# wiring.net
KiCad netlist of a schematic drawn in EAGLE
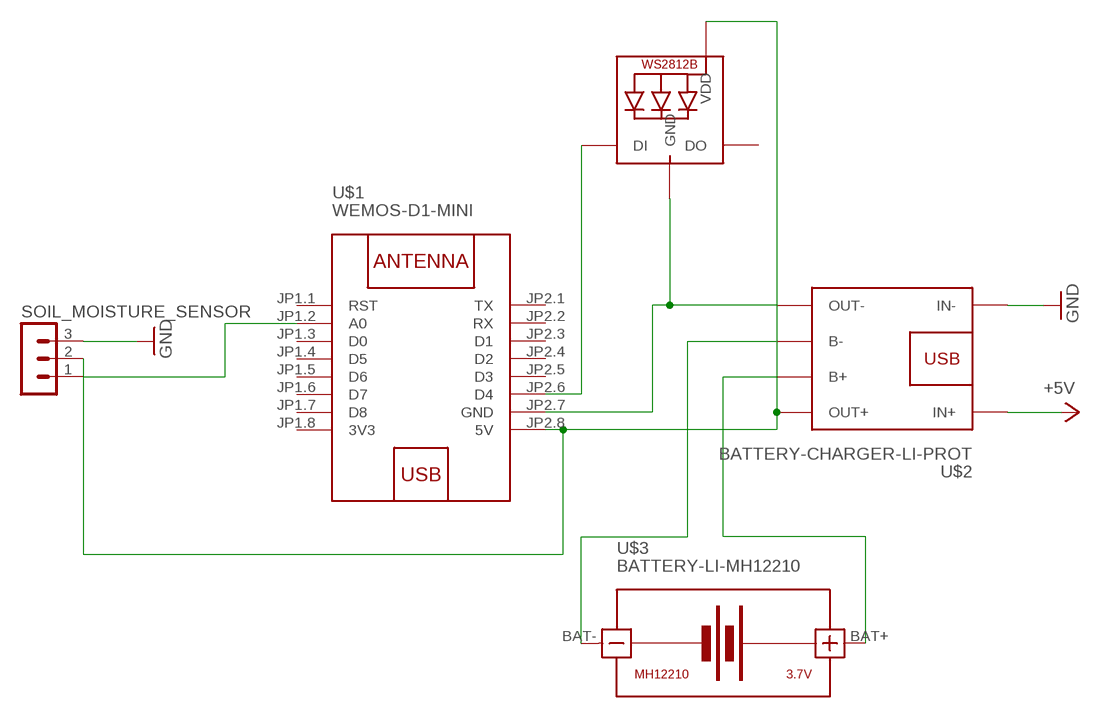
[diagram p0: schematic, sheet 1]

(export (version "E")
  (design (tool "Eeschema 10.0.6"))
  (components
    (comp (ref "LED1")
      (value "WS2812B3535")
      (footprint "eagle-import:LED3535")
      (libsource (lib "eagle-import") (part "WS2812B3535"))
    )
    (comp (ref "SOIL_MOISTURE_SENSOR")
      (value "MA03-1")
      (footprint "eagle-import:MA03-1")
      (libsource (lib "eagle-import") (part "MA03-1"))
    )
    (comp (ref "U$1")
      (value "WEMOS-D1-MINI")
      (footprint "eagle-import:WEMOS-D1-MINI")
      (libsource (lib "eagle-import") (part "WEMOS-D1-MINI"))
    )
    (comp (ref "U$2")
      (value "BATTERY-CHARGER-LI-PROT")
      (footprint "eagle-import:BATTERY-CHARGER-LI-PROT")
      (libsource (lib "eagle-import") (part "BATTERY-CHARGER-LI-PROT"))
    )
    (comp (ref "U$3")
      (value "BATTERY-LI-MH12210")
      (footprint "eagle-import:BATTERY-LI-MH12210")
      (libsource (lib "eagle-import") (part "BATTERY-LI-MH12210"))
    )
  )
  (nets
    (net (code "1") (name "+5V") (class "Default")
      (node (ref "U$2") (pin "IN+") (pinfunction "IN+_IN+") (pintype "bidirectional"))
    )
    (net (code "2") (name "/3V3") (class "Default")
      (node (ref "U$1") (pin "JP1.8") (pinfunction "3V3_JP1.8") (pintype "power_in"))
    )
    (net (code "3") (name "GND") (class "Default")
      (node (ref "SOIL_MOISTURE_SENSOR") (pin "3") (pinfunction "3_3") (pintype "passive"))
      (node (ref "U$2") (pin "IN-") (pinfunction "IN-_IN-") (pintype "bidirectional"))
    )
    (net (code "4") (name "Net-(LED1-DI)") (class "Default")
      (node (ref "LED1") (pin "1") (pinfunction "DI_1") (pintype "input"))
      (node (ref "U$1") (pin "JP2.6") (pinfunction "D4_JP2.6") (pintype "bidirectional"))
    )
    (net (code "5") (name "Net-(LED1-GND)") (class "Default")
      (node (ref "LED1") (pin "4") (pinfunction "GND_4") (pintype "power_in"))
      (node (ref "U$1") (pin "JP2.7") (pinfunction "GND_JP2.7") (pintype "power_in"))
      (node (ref "U$2") (pin "OUT-") (pinfunction "OUT-_OUT-") (pintype "bidirectional"))
    )
    (net (code "6") (name "Net-(LED1-VDD)") (class "Default")
      (node (ref "LED1") (pin "2") (pinfunction "VDD_2") (pintype "power_in"))
      (node (ref "SOIL_MOISTURE_SENSOR") (pin "2") (pinfunction "2_2") (pintype "passive"))
      (node (ref "U$1") (pin "JP2.8") (pinfunction "5V_JP2.8") (pintype "power_in"))
      (node (ref "U$2") (pin "OUT+") (pinfunction "OUT+_OUT+") (pintype "bidirectional"))
    )
    (net (code "7") (name "Net-(U$1-A0)") (class "Default")
      (node (ref "SOIL_MOISTURE_SENSOR") (pin "1") (pinfunction "1_1") (pintype "passive"))
      (node (ref "U$1") (pin "JP1.2") (pinfunction "A0_JP1.2") (pintype "bidirectional"))
    )
    (net (code "8") (name "Net-(U$2-PadB+)") (class "Default")
      (node (ref "U$2") (pin "B+") (pinfunction "B+_B+") (pintype "bidirectional"))
      (node (ref "U$3") (pin "BAT+") (pinfunction "BAT+_BAT+") (pintype "power_in"))
    )
    (net (code "9") (name "Net-(U$2-PadB-)") (class "Default")
      (node (ref "U$2") (pin "B-") (pinfunction "B-_B-") (pintype "bidirectional"))
      (node (ref "U$3") (pin "BAT-") (pinfunction "BAT-_BAT-") (pintype "power_in"))
    )
    (net (code "10") (name "unconnected-(LED1-DO-Pad3)") (class "Default")
      (node (ref "LED1") (pin "3") (pinfunction "DO_3") (pintype "output"))
    )
    (net (code "11") (name "unconnected-(U$1-D0-PadJP1.3)") (class "Default")
      (node (ref "U$1") (pin "JP1.3") (pinfunction "D0_JP1.3") (pintype "bidirectional"))
    )
    (net (code "12") (name "unconnected-(U$1-D1-PadJP2.3)") (class "Default")
      (node (ref "U$1") (pin "JP2.3") (pinfunction "D1_JP2.3") (pintype "bidirectional"))
    )
    (net (code "13") (name "unconnected-(U$1-D2-PadJP2.4)") (class "Default")
      (node (ref "U$1") (pin "JP2.4") (pinfunction "D2_JP2.4") (pintype "bidirectional"))
    )
    (net (code "14") (name "unconnected-(U$1-D3-PadJP2.5)") (class "Default")
      (node (ref "U$1") (pin "JP2.5") (pinfunction "D3_JP2.5") (pintype "bidirectional"))
    )
    (net (code "15") (name "unconnected-(U$1-D5-PadJP1.4)") (class "Default")
      (node (ref "U$1") (pin "JP1.4") (pinfunction "D5_JP1.4") (pintype "bidirectional"))
    )
    (net (code "16") (name "unconnected-(U$1-D6-PadJP1.5)") (class "Default")
      (node (ref "U$1") (pin "JP1.5") (pinfunction "D6_JP1.5") (pintype "bidirectional"))
    )
    (net (code "17") (name "unconnected-(U$1-D7-PadJP1.6)") (class "Default")
      (node (ref "U$1") (pin "JP1.6") (pinfunction "D7_JP1.6") (pintype "bidirectional"))
    )
    (net (code "18") (name "unconnected-(U$1-D8-PadJP1.7)") (class "Default")
      (node (ref "U$1") (pin "JP1.7") (pinfunction "D8_JP1.7") (pintype "bidirectional"))
    )
    (net (code "19") (name "unconnected-(U$1-RST-PadJP1.1)") (class "Default")
      (node (ref "U$1") (pin "JP1.1") (pinfunction "RST_JP1.1") (pintype "bidirectional"))
    )
    (net (code "20") (name "unconnected-(U$1-RX-PadJP2.2)") (class "Default")
      (node (ref "U$1") (pin "JP2.2") (pinfunction "RX_JP2.2") (pintype "bidirectional"))
    )
    (net (code "21") (name "unconnected-(U$1-TX-PadJP2.1)") (class "Default")
      (node (ref "U$1") (pin "JP2.1") (pinfunction "TX_JP2.1") (pintype "bidirectional"))
    )
  )
)
